# DashHub.net
KiCad netlist of a schematic drawn in EAGLE
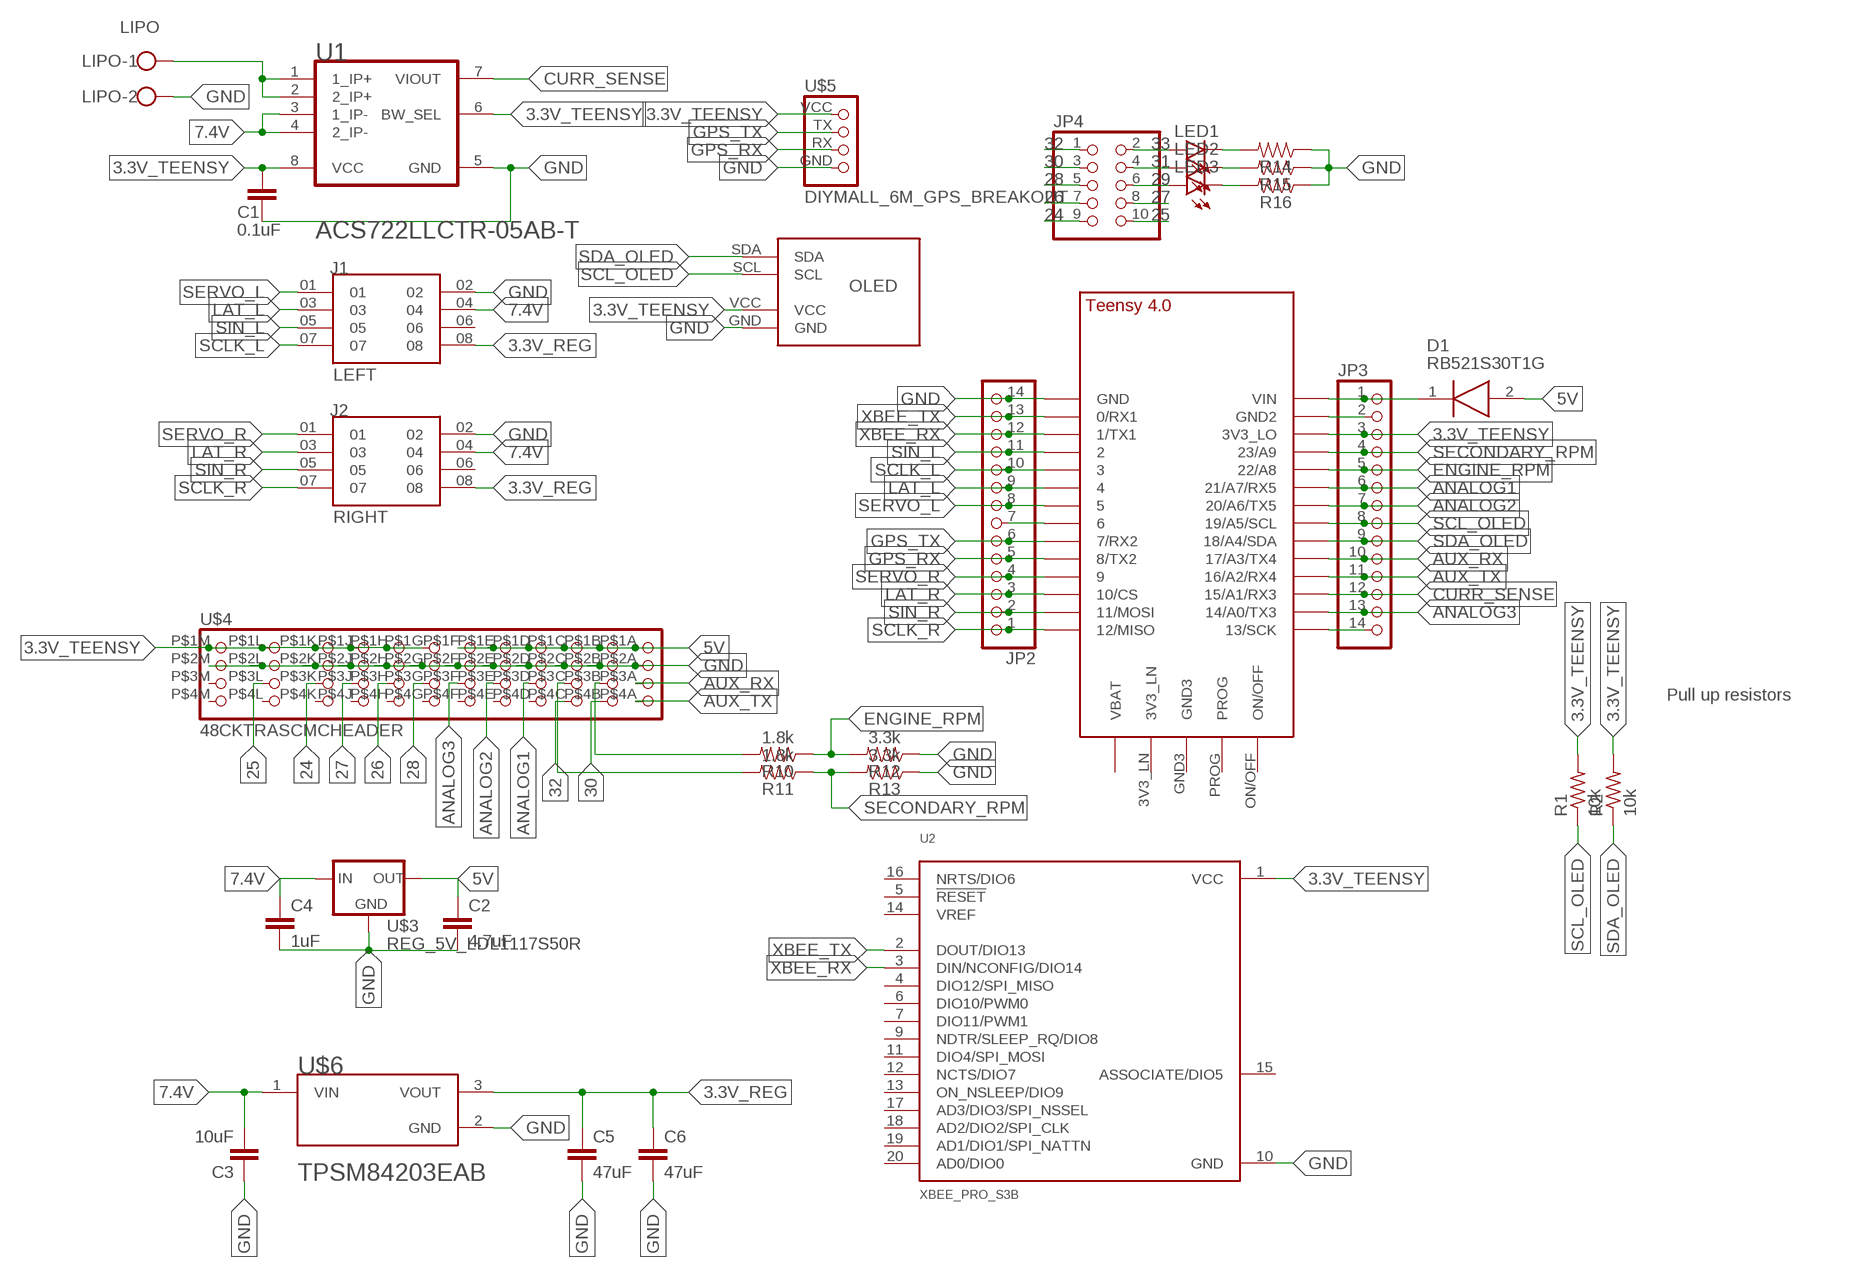
[diagram p0: schematic, sheet 1]

(export (version "E")
  (design (tool "Eeschema 10.0.6"))
  (components
    (comp (ref "C1")
      (value "0.1uF")
      (footprint "eagle-import:C0402")
      (libsource (lib "eagle-import") (part "C-EUC0402"))
    )
    (comp (ref "C2")
      (value "4.7uF")
      (footprint "eagle-import:C0603")
      (libsource (lib "eagle-import") (part "CAP_SMDC0603"))
    )
    (comp (ref "C3")
      (value "10uF")
      (footprint "eagle-import:C1206")
      (libsource (lib "eagle-import") (part "CAP_SMDC1206"))
    )
    (comp (ref "C4")
      (value "1uF")
      (footprint "eagle-import:C1206")
      (libsource (lib "eagle-import") (part "CAP_SMDC1206"))
    )
    (comp (ref "C5")
      (value "47uF")
      (footprint "eagle-import:C1206")
      (libsource (lib "eagle-import") (part "CAP_SMDC1206"))
    )
    (comp (ref "C6")
      (value "47uF")
      (footprint "eagle-import:C1206")
      (libsource (lib "eagle-import") (part "CAP_SMDC1206"))
    )
    (comp (ref "D1")
      (value "RB521S30T1G")
      (footprint "eagle-import:SODFL1608X70N")
      (fields (field (name "MOUSER_PART_NUMBER") "863-RB521S30T1G"))
      (libsource (lib "eagle-import") (part "RB521S30T1G"))
    )
    (comp (ref "J1")
      (value "LEFT")
      (footprint "eagle-import:SAMTEC_ESW-104-23-L-D")
      (fields (field (name "MANUFACTURER") "Samtec Inc."))
      (libsource (lib "eagle-import") (part "ESW-104-23-L-D"))
    )
    (comp (ref "J2")
      (value "RIGHT")
      (footprint "eagle-import:SAMTEC_ESW-104-23-L-D")
      (fields (field (name "MANUFACTURER") "Samtec Inc."))
      (libsource (lib "eagle-import") (part "ESW-104-23-L-D"))
    )
    (comp (ref "JP2")
      (value "PINHD-1X14")
      (footprint "eagle-import:1X14")
      (libsource (lib "eagle-import") (part "PINHD-1X14"))
    )
    (comp (ref "JP3")
      (value "PINHD-1X14")
      (footprint "eagle-import:1X14")
      (libsource (lib "eagle-import") (part "PINHD-1X14"))
    )
    (comp (ref "JP4")
      (value "PINHD-2X5")
      (footprint "eagle-import:2X05")
      (libsource (lib "eagle-import") (part "PINHD-2X5"))
    )
    (comp (ref "LED1")
      (value "LEDCHIPLED_1206")
      (footprint "eagle-import:CHIPLED_1206")
      (libsource (lib "eagle-import") (part "LEDCHIPLED_1206"))
    )
    (comp (ref "LED2")
      (value "LEDCHIPLED_1206")
      (footprint "eagle-import:CHIPLED_1206")
      (libsource (lib "eagle-import") (part "LEDCHIPLED_1206"))
    )
    (comp (ref "LED3")
      (value "LEDCHIPLED_1206")
      (footprint "eagle-import:CHIPLED_1206")
      (libsource (lib "eagle-import") (part "LEDCHIPLED_1206"))
    )
    (comp (ref "LIPO")
      (value "LIPO")
      (footprint "eagle-import:W237-102")
      (fields (field (name "MPN") "237-102"))
      (libsource (lib "eagle-import") (part "W237-102"))
    )
    (comp (ref "R1")
      (value "10k")
      (footprint "eagle-import:R0603")
      (libsource (lib "eagle-import") (part "RES_SMDR0603"))
    )
    (comp (ref "R2")
      (value "10k")
      (footprint "eagle-import:R0603")
      (libsource (lib "eagle-import") (part "RES_SMDR0603"))
    )
    (comp (ref "R10")
      (value "1.8k")
      (footprint "eagle-import:AXIAL-0.3")
      (libsource (lib "eagle-import") (part "RESISTORAXIAL-0.3"))
    )
    (comp (ref "R11")
      (value "1.8k")
      (footprint "eagle-import:AXIAL-0.3")
      (libsource (lib "eagle-import") (part "RESISTORAXIAL-0.3"))
    )
    (comp (ref "R12")
      (value "3.3k")
      (footprint "eagle-import:AXIAL-0.3")
      (libsource (lib "eagle-import") (part "RESISTORAXIAL-0.3"))
    )
    (comp (ref "R13")
      (value "3.3k")
      (footprint "eagle-import:AXIAL-0.3")
      (libsource (lib "eagle-import") (part "RESISTORAXIAL-0.3"))
    )
    (comp (ref "R14")
      (value "RESISTORAXIAL-0.3")
      (footprint "eagle-import:AXIAL-0.3")
      (libsource (lib "eagle-import") (part "RESISTORAXIAL-0.3"))
    )
    (comp (ref "R15")
      (value "RESISTORAXIAL-0.3")
      (footprint "eagle-import:AXIAL-0.3")
      (libsource (lib "eagle-import") (part "RESISTORAXIAL-0.3"))
    )
    (comp (ref "R16")
      (value "RESISTORAXIAL-0.3")
      (footprint "eagle-import:AXIAL-0.3")
      (libsource (lib "eagle-import") (part "RESISTORAXIAL-0.3"))
    )
    (comp (ref "U$1")
      (value "TEENSY_4.0-BASIC")
      (footprint "eagle-import:TEENSY_4.0-BASIC")
      (libsource (lib "eagle-import") (part "TEENSY_4.0-BASIC"))
    )
    (comp (ref "U$2")
      (value "OLED_SSD1306")
      (footprint "eagle-import:OLED_SSD1306")
      (libsource (lib "eagle-import") (part "OLED_SSD1306"))
    )
    (comp (ref "U$3")
      (value "REG_5V_LDL1117S50R")
      (footprint "eagle-import:SOT230P700X180-4N")
      (libsource (lib "eagle-import") (part "REG_5V_LDL1117S50R"))
    )
    (comp (ref "U$4")
      (value "48CKTRASCMCHEADER")
      (footprint "eagle-import:48CKTRASCMCHEADER")
      (libsource (lib "eagle-import") (part "48CKTRASCMCHEADER"))
    )
    (comp (ref "U$5")
      (value "DIYMALL_6M_GPS_BREAKOUT")
      (footprint "eagle-import:DIYMALL_6M_GPS_BREAKOUT")
      (libsource (lib "eagle-import") (part "DIYMALL_6M_GPS_BREAKOUT"))
    )
    (comp (ref "U$6")
      (value "TPSM84205EAB")
      (footprint "eagle-import:TPSM84205EAB")
      (libsource (lib "eagle-import") (part "TPSM84205EAB"))
    )
    (comp (ref "U1")
      (value "ALLEGRO_MICROSYSTEMS_ACS722LLCTR-05AB-TALLEGRO_MICROSYSTEMS_ACS722LLCTR-05AB-T_0_0")
      (footprint "eagle-import:ALLEGRO_MICROSYSTEMS_ACS722LLCTR-05AB-T_0")
      (fields (field (name "MF") "Allegro MicroSystems") (field (name "MPN") "ACS722LLCTR-05AB-T"))
      (libsource (lib "eagle-import") (part "ALLEGRO_MICROSYSTEMS_ACS722LLCTR-05AB-TALLEGRO_MICROSYSTEMS_ACS722LLCTR-05AB-T_0_0"))
    )
    (comp (ref "U2")
      (value "XBEE_PRO_S3B")
      (footprint "eagle-import:XBEE_PRO_S3B")
      (fields
        (field (name "DIGI-KEY_PART_NUMBER") "602-1293-ND")
        (field (name "MF") "Digi International")
        (field (name "MP") "XBP9B-XCST-001")
      )
      (libsource (lib "eagle-import") (part "XBEE_PRO_S3B"))
    )
  )
  (nets
    (net (code "1") (name "/29") (class "Default")
      (node (ref "JP4") (pin "6") (pinfunction "6_6") (pintype "passive"))
      (node (ref "LED3") (pin "A") (pinfunction "A_A") (pintype "passive"))
    )
    (net (code "2") (name "/31") (class "Default")
      (node (ref "JP4") (pin "4") (pinfunction "4_4") (pintype "passive"))
      (node (ref "LED2") (pin "A") (pinfunction "A_A") (pintype "passive"))
    )
    (net (code "3") (name "/33") (class "Default")
      (node (ref "JP4") (pin "2") (pinfunction "2_2") (pintype "passive"))
      (node (ref "LED1") (pin "A") (pinfunction "A_A") (pintype "passive"))
    )
    (net (code "4") (name "3.3V_REG") (class "Default")
      (node (ref "C5") (pin "1") (pinfunction "1_1") (pintype "passive"))
      (node (ref "C6") (pin "1") (pinfunction "1_1") (pintype "passive"))
      (node (ref "J1") (pin "08") (pinfunction "08_08") (pintype "passive"))
      (node (ref "J2") (pin "08") (pinfunction "08_08") (pintype "passive"))
      (node (ref "U$6") (pin "3") (pinfunction "VOUT_3") (pintype "power_in"))
    )
    (net (code "5") (name "3.3V_TEENSY") (class "Default")
      (node (ref "C1") (pin "2") (pinfunction "2_2") (pintype "passive"))
      (node (ref "JP3") (pin "3") (pinfunction "3_3") (pintype "passive"))
      (node (ref "R1") (pin "2") (pinfunction "2_2") (pintype "passive"))
      (node (ref "R2") (pin "2") (pinfunction "2_2") (pintype "passive"))
      (node (ref "U$1") (pin "3V3_LO") (pinfunction "3V3_LO_3V3_LO") (pintype "bidirectional"))
      (node (ref "U$2") (pin "VCC") (pinfunction "VCC_VCC") (pintype "bidirectional"))
      (node (ref "U$4") (pin "P$1G") (pinfunction "1G_P$1G") (pintype "passive"))
      (node (ref "U$4") (pin "P$1H") (pinfunction "1H_P$1H") (pintype "passive"))
      (node (ref "U$4") (pin "P$1J") (pinfunction "1J_P$1J") (pintype "passive"))
      (node (ref "U$4") (pin "P$1K") (pinfunction "1K_P$1K") (pintype "passive"))
      (node (ref "U$4") (pin "P$1L") (pinfunction "1L_P$1L") (pintype "passive"))
      (node (ref "U$4") (pin "P$1M") (pinfunction "1M_P$1M") (pintype "passive"))
      (node (ref "U$5") (pin "VCC") (pinfunction "VCC_VCC") (pintype "passive"))
      (node (ref "U1") (pin "6") (pinfunction "BW_SEL_6") (pintype "input"))
      (node (ref "U1") (pin "8") (pinfunction "VCC_8") (pintype "power_in"))
      (node (ref "U2") (pin "1") (pinfunction "VCC_1") (pintype "power_in"))
    )
    (net (code "6") (name "5V") (class "Default")
      (node (ref "C2") (pin "1") (pinfunction "1_1") (pintype "passive"))
      (node (ref "D1") (pin "2") (pinfunction "A_2") (pintype "bidirectional"))
      (node (ref "U$3") (pin "2") (pinfunction "OUT_2") (pintype "output"))
      (node (ref "U$3") (pin "4") (pinfunction "OUT_4") (pintype "output"))
      (node (ref "U$4") (pin "P$1A") (pinfunction "1A_P$1A") (pintype "passive"))
      (node (ref "U$4") (pin "P$1B") (pinfunction "1B_P$1B") (pintype "passive"))
      (node (ref "U$4") (pin "P$1C") (pinfunction "1C_P$1C") (pintype "passive"))
      (node (ref "U$4") (pin "P$1D") (pinfunction "1D_P$1D") (pintype "passive"))
      (node (ref "U$4") (pin "P$1E") (pinfunction "1E_P$1E") (pintype "passive"))
      (node (ref "U$4") (pin "P$1F") (pinfunction "1F_P$1F") (pintype "passive"))
    )
    (net (code "7") (name "7.4V") (class "Default")
      (node (ref "C3") (pin "2") (pinfunction "2_2") (pintype "passive"))
      (node (ref "C4") (pin "1") (pinfunction "1_1") (pintype "passive"))
      (node (ref "J1") (pin "04") (pinfunction "04_04") (pintype "passive"))
      (node (ref "J2") (pin "04") (pinfunction "04_04") (pintype "passive"))
      (node (ref "U$3") (pin "3") (pinfunction "IN_3") (pintype "input"))
      (node (ref "U$6") (pin "1") (pinfunction "VIN_1") (pintype "power_in"))
      (node (ref "U1") (pin "3") (pinfunction "1_IP-_3") (pintype "input"))
      (node (ref "U1") (pin "4") (pinfunction "2_IP-_4") (pintype "input"))
    )
    (net (code "8") (name "24") (class "Default")
      (node (ref "JP4") (pin "9") (pinfunction "9_9") (pintype "passive"))
      (node (ref "U$4") (pin "P$3K") (pinfunction "3K_P$3K") (pintype "passive"))
    )
    (net (code "9") (name "25") (class "Default")
      (node (ref "JP4") (pin "10") (pinfunction "10_10") (pintype "passive"))
      (node (ref "U$4") (pin "P$3L") (pinfunction "3L_P$3L") (pintype "passive"))
    )
    (net (code "10") (name "26") (class "Default")
      (node (ref "JP4") (pin "7") (pinfunction "7_7") (pintype "passive"))
      (node (ref "U$4") (pin "P$3H") (pinfunction "3H_P$3H") (pintype "passive"))
    )
    (net (code "11") (name "27") (class "Default")
      (node (ref "JP4") (pin "8") (pinfunction "8_8") (pintype "passive"))
      (node (ref "U$4") (pin "P$3J") (pinfunction "3J_P$3J") (pintype "passive"))
    )
    (net (code "12") (name "28") (class "Default")
      (node (ref "JP4") (pin "5") (pinfunction "5_5") (pintype "passive"))
      (node (ref "U$4") (pin "P$3G") (pinfunction "3G_P$3G") (pintype "passive"))
    )
    (net (code "13") (name "30") (class "Default")
      (node (ref "JP4") (pin "3") (pinfunction "3_3") (pintype "passive"))
      (node (ref "U$4") (pin "P$4B") (pinfunction "4B_P$4B") (pintype "passive"))
    )
    (net (code "14") (name "32") (class "Default")
      (node (ref "JP4") (pin "1") (pinfunction "1_1") (pintype "passive"))
      (node (ref "U$4") (pin "P$4C") (pinfunction "4C_P$4C") (pintype "passive"))
    )
    (net (code "15") (name "ANALOG1") (class "Default")
      (node (ref "JP3") (pin "6") (pinfunction "6_6") (pintype "passive"))
      (node (ref "U$1") (pin "21/A7") (pinfunction "21/A7/RX5_21/A7") (pintype "bidirectional"))
      (node (ref "U$4") (pin "P$3D") (pinfunction "3D_P$3D") (pintype "passive"))
    )
    (net (code "16") (name "ANALOG2") (class "Default")
      (node (ref "JP3") (pin "7") (pinfunction "7_7") (pintype "passive"))
      (node (ref "U$1") (pin "20/A6") (pinfunction "20/A6/TX5_20/A6") (pintype "bidirectional"))
      (node (ref "U$4") (pin "P$3E") (pinfunction "3E_P$3E") (pintype "passive"))
    )
    (net (code "17") (name "ANALOG3") (class "Default")
      (node (ref "JP3") (pin "13") (pinfunction "13_13") (pintype "passive"))
      (node (ref "U$1") (pin "14/A0") (pinfunction "14/A0/TX3_14/A0") (pintype "bidirectional"))
      (node (ref "U$4") (pin "P$3F") (pinfunction "3F_P$3F") (pintype "passive"))
    )
    (net (code "18") (name "AUX_RX") (class "Default")
      (node (ref "JP3") (pin "10") (pinfunction "10_10") (pintype "passive"))
      (node (ref "U$1") (pin "17/A3") (pinfunction "17/A3/TX4_17/A3") (pintype "bidirectional"))
      (node (ref "U$4") (pin "P$3A") (pinfunction "3A_P$3A") (pintype "passive"))
    )
    (net (code "19") (name "AUX_TX") (class "Default")
      (node (ref "JP3") (pin "11") (pinfunction "11_11") (pintype "passive"))
      (node (ref "U$1") (pin "16/A2") (pinfunction "16/A2/RX4_16/A2") (pintype "bidirectional"))
      (node (ref "U$4") (pin "P$4A") (pinfunction "4A_P$4A") (pintype "passive"))
    )
    (net (code "20") (name "CURR_SENSE") (class "Default")
      (node (ref "JP3") (pin "12") (pinfunction "12_12") (pintype "passive"))
      (node (ref "U$1") (pin "15/A1") (pinfunction "15/A1/RX3_15/A1") (pintype "bidirectional"))
      (node (ref "U1") (pin "7") (pinfunction "VIOUT_7") (pintype "output"))
    )
    (net (code "21") (name "ENGINE_RPM") (class "Default")
      (node (ref "JP3") (pin "5") (pinfunction "5_5") (pintype "passive"))
      (node (ref "R10") (pin "P$1") (pinfunction "1_P$1") (pintype "passive"))
      (node (ref "R12") (pin "P$2") (pinfunction "2_P$2") (pintype "passive"))
      (node (ref "U$1") (pin "22/A8") (pinfunction "22/A8_22/A8") (pintype "bidirectional"))
    )
    (net (code "22") (name "GND") (class "Default")
      (node (ref "C1") (pin "1") (pinfunction "1_1") (pintype "passive"))
      (node (ref "C2") (pin "2") (pinfunction "2_2") (pintype "passive"))
      (node (ref "C3") (pin "1") (pinfunction "1_1") (pintype "passive"))
      (node (ref "C4") (pin "2") (pinfunction "2_2") (pintype "passive"))
      (node (ref "C5") (pin "2") (pinfunction "2_2") (pintype "passive"))
      (node (ref "C6") (pin "2") (pinfunction "2_2") (pintype "passive"))
      (node (ref "J1") (pin "02") (pinfunction "02_02") (pintype "passive"))
      (node (ref "J2") (pin "02") (pinfunction "02_02") (pintype "passive"))
      (node (ref "JP2") (pin "14") (pinfunction "14_14") (pintype "passive"))
      (node (ref "LIPO") (pin "2") (pinfunction "KL_2") (pintype "passive"))
      (node (ref "R12") (pin "P$1") (pinfunction "1_P$1") (pintype "passive"))
      (node (ref "R13") (pin "P$1") (pinfunction "1_P$1") (pintype "passive"))
      (node (ref "R14") (pin "P$1") (pinfunction "1_P$1") (pintype "passive"))
      (node (ref "R15") (pin "P$1") (pinfunction "1_P$1") (pintype "passive"))
      (node (ref "R16") (pin "P$1") (pinfunction "1_P$1") (pintype "passive"))
      (node (ref "U$1") (pin "GND") (pinfunction "GND_GND") (pintype "bidirectional"))
      (node (ref "U$2") (pin "GND") (pinfunction "GND_GND") (pintype "bidirectional"))
      (node (ref "U$3") (pin "1") (pinfunction "GND_1") (pintype "input"))
      (node (ref "U$4") (pin "P$2A") (pinfunction "2A_P$2A") (pintype "passive"))
      (node (ref "U$4") (pin "P$2B") (pinfunction "2B_P$2B") (pintype "passive"))
      (node (ref "U$4") (pin "P$2C") (pinfunction "2C_P$2C") (pintype "passive"))
      (node (ref "U$4") (pin "P$2D") (pinfunction "2D_P$2D") (pintype "passive"))
      (node (ref "U$4") (pin "P$2E") (pinfunction "2E_P$2E") (pintype "passive"))
      (node (ref "U$4") (pin "P$2F") (pinfunction "2F_P$2F") (pintype "passive"))
      (node (ref "U$4") (pin "P$2G") (pinfunction "2G_P$2G") (pintype "passive"))
      (node (ref "U$4") (pin "P$2H") (pinfunction "2H_P$2H") (pintype "passive"))
      (node (ref "U$4") (pin "P$2J") (pinfunction "2J_P$2J") (pintype "passive"))
      (node (ref "U$4") (pin "P$2K") (pinfunction "2K_P$2K") (pintype "passive"))
      (node (ref "U$4") (pin "P$2L") (pinfunction "2L_P$2L") (pintype "passive"))
      (node (ref "U$4") (pin "P$2M") (pinfunction "2M_P$2M") (pintype "passive"))
      (node (ref "U$5") (pin "GND") (pinfunction "GND_GND") (pintype "passive"))
      (node (ref "U$6") (pin "2") (pinfunction "GND_2") (pintype "power_in"))
      (node (ref "U1") (pin "5") (pinfunction "GND_5") (pintype "power_in"))
      (node (ref "U2") (pin "10") (pinfunction "GND_10") (pintype "power_in"))
    )
    (net (code "23") (name "GPS_RX") (class "Default")
      (node (ref "JP2") (pin "5") (pinfunction "5_5") (pintype "passive"))
      (node (ref "U$1") (pin "8") (pinfunction "8/TX2_8") (pintype "bidirectional"))
      (node (ref "U$5") (pin "RX") (pinfunction "RX_RX") (pintype "passive"))
    )
    (net (code "24") (name "GPS_TX") (class "Default")
      (node (ref "JP2") (pin "6") (pinfunction "6_6") (pintype "passive"))
      (node (ref "U$1") (pin "7") (pinfunction "7/RX2_7") (pintype "bidirectional"))
      (node (ref "U$5") (pin "TX") (pinfunction "TX_TX") (pintype "passive"))
    )
    (net (code "25") (name "LAT_L") (class "Default")
      (node (ref "J1") (pin "03") (pinfunction "03_03") (pintype "passive"))
      (node (ref "JP2") (pin "9") (pinfunction "9_9") (pintype "passive"))
      (node (ref "U$1") (pin "4/CANRX") (pinfunction "4_4/CANRX") (pintype "bidirectional"))
    )
    (net (code "26") (name "LAT_R") (class "Default")
      (node (ref "J2") (pin "03") (pinfunction "03_03") (pintype "passive"))
      (node (ref "JP2") (pin "3") (pinfunction "3_3") (pintype "passive"))
      (node (ref "U$1") (pin "10/CS") (pinfunction "10/CS_10/CS") (pintype "bidirectional"))
    )
    (net (code "27") (name "Net-(D1-K)") (class "Default")
      (node (ref "D1") (pin "1") (pinfunction "K_1") (pintype "bidirectional"))
      (node (ref "JP3") (pin "1") (pinfunction "1_1") (pintype "passive"))
      (node (ref "U$1") (pin "VIN") (pinfunction "VIN_VIN") (pintype "bidirectional"))
    )
    (net (code "28") (name "Net-(JP2-Pad7)") (class "Default")
      (node (ref "JP2") (pin "7") (pinfunction "7_7") (pintype "passive"))
      (node (ref "U$1") (pin "6") (pinfunction "6_6") (pintype "bidirectional"))
    )
    (net (code "29") (name "Net-(JP3-Pad2)") (class "Default")
      (node (ref "JP3") (pin "2") (pinfunction "2_2") (pintype "passive"))
      (node (ref "U$1") (pin "GND2") (pinfunction "GND2_GND2") (pintype "bidirectional"))
    )
    (net (code "30") (name "Net-(JP3-Pad14)") (class "Default")
      (node (ref "JP3") (pin "14") (pinfunction "14_14") (pintype "passive"))
      (node (ref "U$1") (pin "13/SCK") (pinfunction "13/SCK_13/SCK") (pintype "bidirectional"))
    )
    (net (code "31") (name "Net-(LIPOA-KL)") (class "Default")
      (node (ref "LIPO") (pin "1") (pinfunction "KL_1") (pintype "passive"))
      (node (ref "U1") (pin "1") (pinfunction "1_IP+_1") (pintype "input"))
      (node (ref "U1") (pin "2") (pinfunction "2_IP+_2") (pintype "input"))
    )
    (net (code "32") (name "Net-(R10-2)") (class "Default")
      (node (ref "R10") (pin "P$2") (pinfunction "2_P$2") (pintype "passive"))
      (node (ref "U$4") (pin "P$3B") (pinfunction "3B_P$3B") (pintype "passive"))
    )
    (net (code "33") (name "Net-(R11-2)") (class "Default")
      (node (ref "R11") (pin "P$2") (pinfunction "2_P$2") (pintype "passive"))
      (node (ref "U$4") (pin "P$3C") (pinfunction "3C_P$3C") (pintype "passive"))
    )
    (net (code "34") (name "Net-(R14-2)") (class "Default")
      (node (ref "LED1") (pin "C") (pinfunction "C_C") (pintype "passive"))
      (node (ref "R14") (pin "P$2") (pinfunction "2_P$2") (pintype "passive"))
    )
    (net (code "35") (name "Net-(R15-2)") (class "Default")
      (node (ref "LED2") (pin "C") (pinfunction "C_C") (pintype "passive"))
      (node (ref "R15") (pin "P$2") (pinfunction "2_P$2") (pintype "passive"))
    )
    (net (code "36") (name "Net-(R16-2)") (class "Default")
      (node (ref "LED3") (pin "C") (pinfunction "C_C") (pintype "passive"))
      (node (ref "R16") (pin "P$2") (pinfunction "2_P$2") (pintype "passive"))
    )
    (net (code "37") (name "SCLK_L") (class "Default")
      (node (ref "J1") (pin "07") (pinfunction "07_07") (pintype "passive"))
      (node (ref "JP2") (pin "10") (pinfunction "10_10") (pintype "passive"))
      (node (ref "U$1") (pin "3/CANTX") (pinfunction "3_3/CANTX") (pintype "bidirectional"))
    )
    (net (code "38") (name "SCLK_R") (class "Default")
      (node (ref "J2") (pin "07") (pinfunction "07_07") (pintype "passive"))
      (node (ref "JP2") (pin "1") (pinfunction "1_1") (pintype "passive"))
      (node (ref "U$1") (pin "12/MISO") (pinfunction "12/MISO_12/MISO") (pintype "bidirectional"))
    )
    (net (code "39") (name "SCL_OLED") (class "Default")
      (node (ref "JP3") (pin "8") (pinfunction "8_8") (pintype "passive"))
      (node (ref "R1") (pin "1") (pinfunction "1_1") (pintype "passive"))
      (node (ref "U$1") (pin "19/A5/SCL") (pinfunction "19/A5/SCL_19/A5/SCL") (pintype "bidirectional"))
      (node (ref "U$2") (pin "SCL") (pinfunction "SCL_SCL") (pintype "bidirectional"))
    )
    (net (code "40") (name "SDA_OLED") (class "Default")
      (node (ref "JP3") (pin "9") (pinfunction "9_9") (pintype "passive"))
      (node (ref "R2") (pin "1") (pinfunction "1_1") (pintype "passive"))
      (node (ref "U$1") (pin "18/A4/SDA") (pinfunction "18/A4/SDA_18/A4/SDA") (pintype "bidirectional"))
      (node (ref "U$2") (pin "SDA") (pinfunction "SDA_SDA") (pintype "bidirectional"))
    )
    (net (code "41") (name "SECONDARY_RPM") (class "Default")
      (node (ref "JP3") (pin "4") (pinfunction "4_4") (pintype "passive"))
      (node (ref "R11") (pin "P$1") (pinfunction "1_P$1") (pintype "passive"))
      (node (ref "R13") (pin "P$2") (pinfunction "2_P$2") (pintype "passive"))
      (node (ref "U$1") (pin "23/A9") (pinfunction "23/A9_23/A9") (pintype "bidirectional"))
    )
    (net (code "42") (name "SERVO_L") (class "Default")
      (node (ref "J1") (pin "01") (pinfunction "01_01") (pintype "passive"))
      (node (ref "JP2") (pin "8") (pinfunction "8_8") (pintype "passive"))
      (node (ref "U$1") (pin "5") (pinfunction "5_5") (pintype "bidirectional"))
    )
    (net (code "43") (name "SERVO_R") (class "Default")
      (node (ref "J2") (pin "01") (pinfunction "01_01") (pintype "passive"))
      (node (ref "JP2") (pin "4") (pinfunction "4_4") (pintype "passive"))
      (node (ref "U$1") (pin "9/CS") (pinfunction "9_9/CS") (pintype "bidirectional"))
    )
    (net (code "44") (name "SIN_L") (class "Default")
      (node (ref "J1") (pin "05") (pinfunction "05_05") (pintype "passive"))
      (node (ref "JP2") (pin "11") (pinfunction "11_11") (pintype "passive"))
      (node (ref "U$1") (pin "2") (pinfunction "2_2") (pintype "bidirectional"))
    )
    (net (code "45") (name "SIN_R") (class "Default")
      (node (ref "J2") (pin "05") (pinfunction "05_05") (pintype "passive"))
      (node (ref "JP2") (pin "2") (pinfunction "2_2") (pintype "passive"))
      (node (ref "U$1") (pin "11/MOSI") (pinfunction "11/MOSI_11/MOSI") (pintype "bidirectional"))
    )
    (net (code "46") (name "XBEE_RX") (class "Default")
      (node (ref "JP2") (pin "12") (pinfunction "12_12") (pintype "passive"))
      (node (ref "U$1") (pin "1/TX") (pinfunction "1/TX1_1/TX") (pintype "bidirectional"))
      (node (ref "U2") (pin "3") (pinfunction "DIN/NCONFIG/DIO14_3") (pintype "bidirectional"))
    )
    (net (code "47") (name "XBEE_TX") (class "Default")
      (node (ref "JP2") (pin "13") (pinfunction "13_13") (pintype "passive"))
      (node (ref "U$1") (pin "0/RX") (pinfunction "0/RX1_0/RX") (pintype "bidirectional"))
      (node (ref "U2") (pin "2") (pinfunction "DOUT/DIO13_2") (pintype "bidirectional"))
    )
    (net (code "48") (name "unconnected-(J1-Pad06)") (class "Default")
      (node (ref "J1") (pin "06") (pinfunction "06_06") (pintype "passive"))
    )
    (net (code "49") (name "unconnected-(J2-Pad06)") (class "Default")
      (node (ref "J2") (pin "06") (pinfunction "06_06") (pintype "passive"))
    )
    (net (code "50") (name "unconnected-(U$1-Pad3V3_LN)") (class "Default")
      (node (ref "U$1") (pin "3V3_LN") (pinfunction "3V3_LN_3V3_LN") (pintype "bidirectional"))
    )
    (net (code "51") (name "unconnected-(U$1-PadGND3)") (class "Default")
      (node (ref "U$1") (pin "GND3") (pinfunction "GND3_GND3") (pintype "bidirectional"))
    )
    (net (code "52") (name "unconnected-(U$1-PadON{slash}OFF)") (class "Default")
      (node (ref "U$1") (pin "ON/OFF") (pinfunction "ON/OFF_ON/OFF") (pintype "bidirectional"))
    )
    (net (code "53") (name "unconnected-(U$1-PadPROG)") (class "Default")
      (node (ref "U$1") (pin "PROG") (pinfunction "PROG_PROG") (pintype "bidirectional"))
    )
    (net (code "54") (name "unconnected-(U$1-VBAT-PadVBAT\\)") (class "Default")
      (node (ref "U$1") (pin "VBAT\\") (pinfunction "VBAT_VBAT\\") (pintype "bidirectional"))
    )
    (net (code "55") (name "unconnected-(U$4-3M-PadP$3M)") (class "Default")
      (node (ref "U$4") (pin "P$3M") (pinfunction "3M_P$3M") (pintype "passive"))
    )
    (net (code "56") (name "unconnected-(U$4-4D-PadP$4D)") (class "Default")
      (node (ref "U$4") (pin "P$4D") (pinfunction "4D_P$4D") (pintype "passive"))
    )
    (net (code "57") (name "unconnected-(U$4-4E-PadP$4E)") (class "Default")
      (node (ref "U$4") (pin "P$4E") (pinfunction "4E_P$4E") (pintype "passive"))
    )
    (net (code "58") (name "unconnected-(U$4-4F-PadP$4F)") (class "Default")
      (node (ref "U$4") (pin "P$4F") (pinfunction "4F_P$4F") (pintype "passive"))
    )
    (net (code "59") (name "unconnected-(U$4-4G-PadP$4G)") (class "Default")
      (node (ref "U$4") (pin "P$4G") (pinfunction "4G_P$4G") (pintype "passive"))
    )
    (net (code "60") (name "unconnected-(U$4-4H-PadP$4H)") (class "Default")
      (node (ref "U$4") (pin "P$4H") (pinfunction "4H_P$4H") (pintype "passive"))
    )
    (net (code "61") (name "unconnected-(U$4-4J-PadP$4J)") (class "Default")
      (node (ref "U$4") (pin "P$4J") (pinfunction "4J_P$4J") (pintype "passive"))
    )
    (net (code "62") (name "unconnected-(U$4-4K-PadP$4K)") (class "Default")
      (node (ref "U$4") (pin "P$4K") (pinfunction "4K_P$4K") (pintype "passive"))
    )
    (net (code "63") (name "unconnected-(U$4-4L-PadP$4L)") (class "Default")
      (node (ref "U$4") (pin "P$4L") (pinfunction "4L_P$4L") (pintype "passive"))
    )
    (net (code "64") (name "unconnected-(U$4-4M-PadP$4M)") (class "Default")
      (node (ref "U$4") (pin "P$4M") (pinfunction "4M_P$4M") (pintype "passive"))
    )
    (net (code "65") (name "unconnected-(U2-AD0{slash}DIO0-Pad20)") (class "Default")
      (node (ref "U2") (pin "20") (pinfunction "AD0/DIO0_20") (pintype "bidirectional"))
    )
    (net (code "66") (name "unconnected-(U2-AD1{slash}DIO1{slash}SPI_NATTN-Pad19)") (class "Default")
      (node (ref "U2") (pin "19") (pinfunction "AD1/DIO1/SPI_NATTN_19") (pintype "bidirectional"))
    )
    (net (code "67") (name "unconnected-(U2-AD2{slash}DIO2{slash}SPI_CLK-Pad18)") (class "Default")
      (node (ref "U2") (pin "18") (pinfunction "AD2/DIO2/SPI_CLK_18") (pintype "bidirectional"))
    )
    (net (code "68") (name "unconnected-(U2-AD3{slash}DIO3{slash}SPI_NSSEL-Pad17)") (class "Default")
      (node (ref "U2") (pin "17") (pinfunction "AD3/DIO3/SPI_NSSEL_17") (pintype "bidirectional"))
    )
    (net (code "69") (name "unconnected-(U2-ASSOCIATE{slash}DIO5-Pad15)") (class "Default")
      (node (ref "U2") (pin "15") (pinfunction "ASSOCIATE/DIO5_15") (pintype "output"))
    )
    (net (code "70") (name "unconnected-(U2-DIO4{slash}SPI_MOSI-Pad11)") (class "Default")
      (node (ref "U2") (pin "11") (pinfunction "DIO4/SPI_MOSI_11") (pintype "bidirectional"))
    )
    (net (code "71") (name "unconnected-(U2-DIO10{slash}PWM0-Pad6)") (class "Default")
      (node (ref "U2") (pin "6") (pinfunction "DIO10/PWM0_6") (pintype "bidirectional"))
    )
    (net (code "72") (name "unconnected-(U2-DIO11{slash}PWM1-Pad7)") (class "Default")
      (node (ref "U2") (pin "7") (pinfunction "DIO11/PWM1_7") (pintype "bidirectional"))
    )
    (net (code "73") (name "unconnected-(U2-DIO12{slash}SPI_MISO-Pad4)") (class "Default")
      (node (ref "U2") (pin "4") (pinfunction "DIO12/SPI_MISO_4") (pintype "bidirectional"))
    )
    (net (code "74") (name "unconnected-(U2-NCTS{slash}DIO7-Pad12)") (class "Default")
      (node (ref "U2") (pin "12") (pinfunction "NCTS/DIO7_12") (pintype "bidirectional"))
    )
    (net (code "75") (name "unconnected-(U2-NDTR{slash}SLEEP_RQ{slash}DIO8-Pad9)") (class "Default")
      (node (ref "U2") (pin "9") (pinfunction "NDTR/SLEEP_RQ/DIO8_9") (pintype "bidirectional"))
    )
    (net (code "76") (name "unconnected-(U2-NRTS{slash}DIO6-Pad16)") (class "Default")
      (node (ref "U2") (pin "16") (pinfunction "NRTS/DIO6_16") (pintype "input"))
    )
    (net (code "77") (name "unconnected-(U2-ON_NSLEEP{slash}DIO9-Pad13)") (class "Default")
      (node (ref "U2") (pin "13") (pinfunction "ON_NSLEEP/DIO9_13") (pintype "bidirectional"))
    )
    (net (code "78") (name "unconnected-(U2-VREF-Pad14)") (class "Default")
      (node (ref "U2") (pin "14") (pinfunction "VREF_14") (pintype "input"))
    )
    (net (code "79") (name "unconnected-(U2-~{RESET}-Pad5)") (class "Default")
      (node (ref "U2") (pin "5") (pinfunction "~{RESET}_5") (pintype "input"))
    )
  )
)
